# Ai_Breakout_BME280.net
KiCad netlist of a schematic drawn in EAGLE
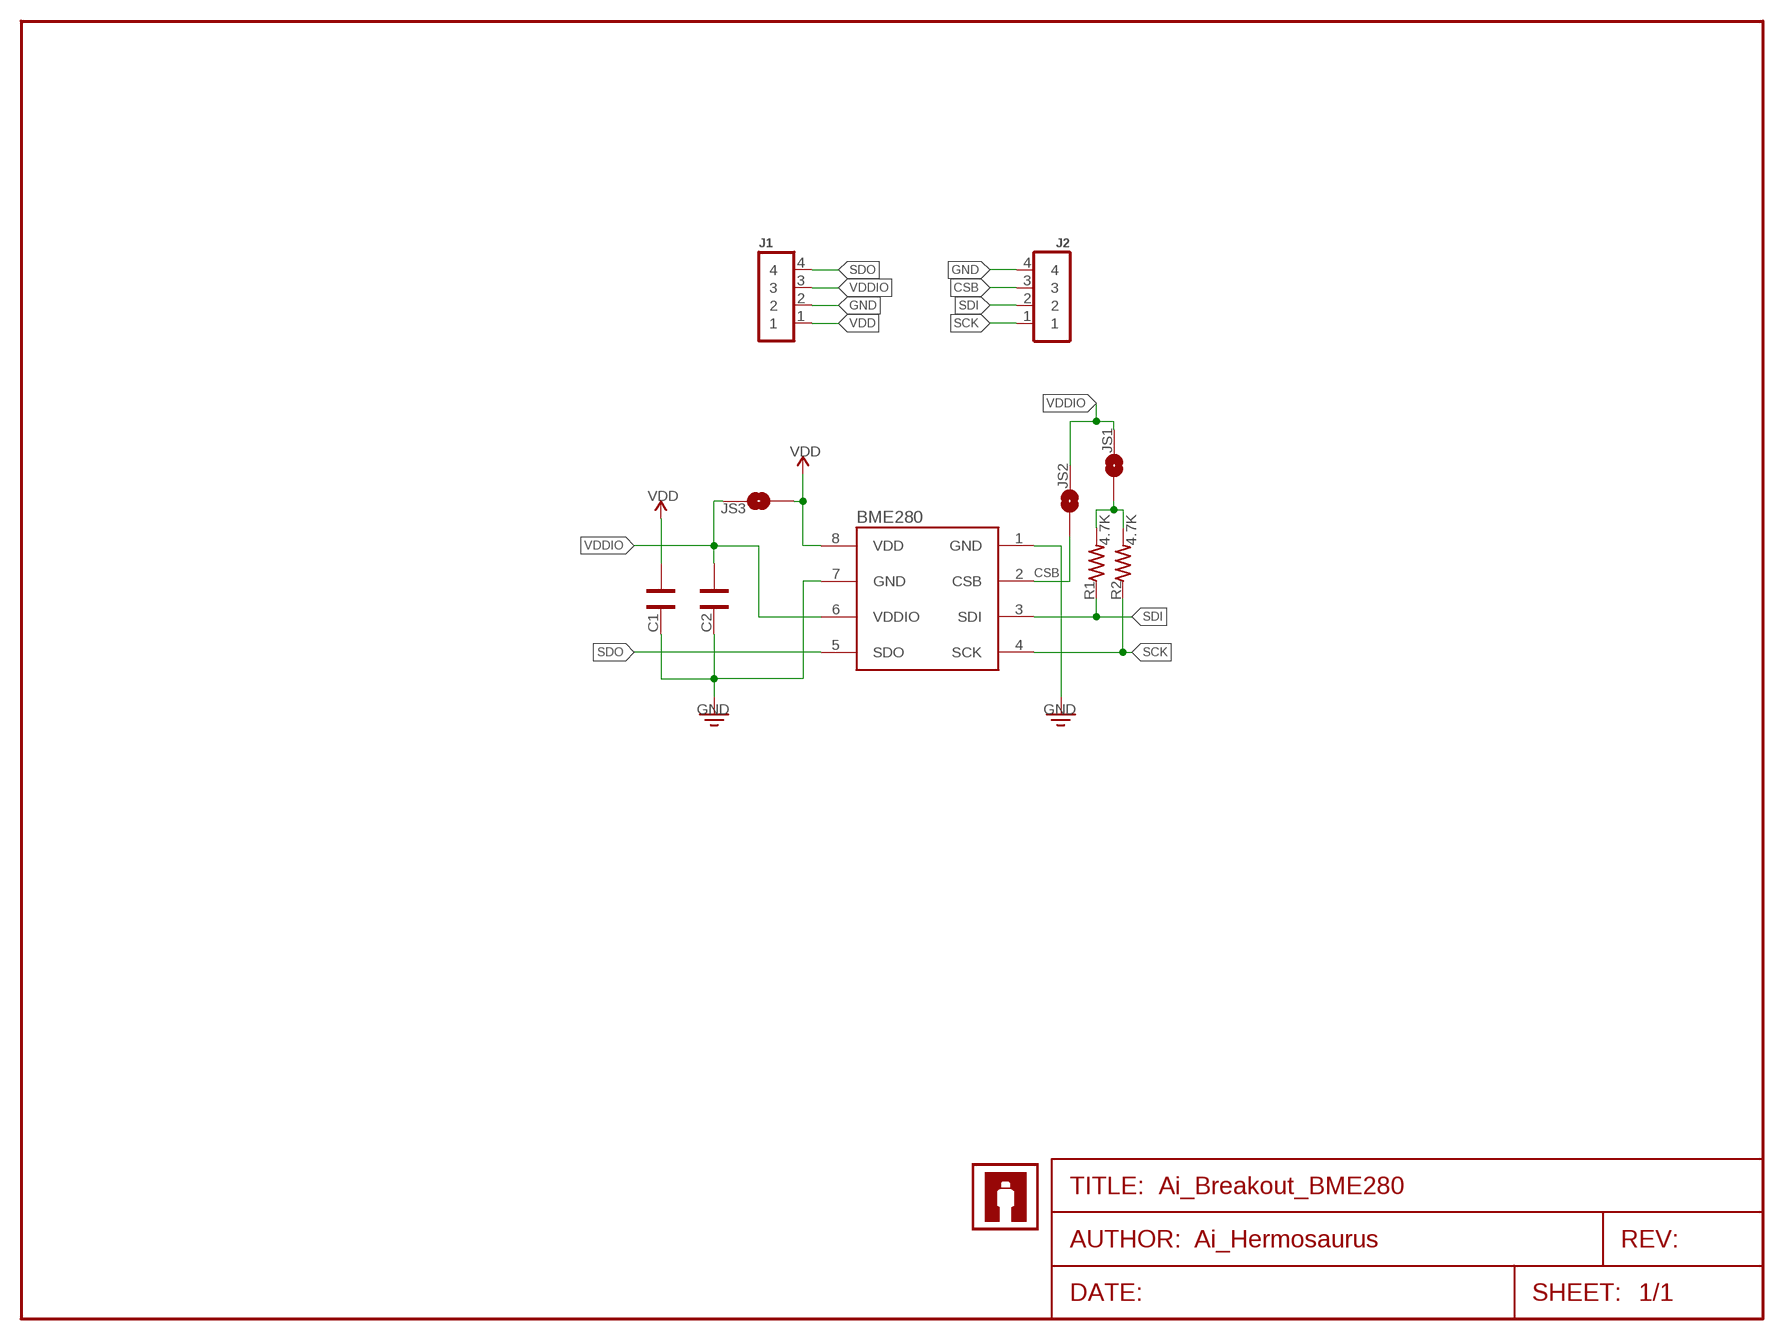
[diagram p0: schematic, sheet 1]

(export (version "E")
  (design (tool "Eeschema 10.0.6"))
  (components
    (comp (ref "C1")
      (value "CAP0603")
      (footprint "eagle-import:CAP-0603")
      (libsource (lib "eagle-import") (part "CAP0603"))
    )
    (comp (ref "C2")
      (value "CAP0603")
      (footprint "eagle-import:CAP-0603")
      (libsource (lib "eagle-import") (part "CAP0603"))
    )
    (comp (ref "J1")
      (value "1X04")
      (footprint "eagle-import:1X04")
      (libsource (lib "eagle-import") (part "1X04"))
    )
    (comp (ref "J2")
      (value "1X04NOFIRST")
      (footprint "eagle-import:1X04-NOFIRST")
      (libsource (lib "eagle-import") (part "1X04NOFIRST"))
    )
    (comp (ref "JS1")
      (value "1X02-SJ-NO")
      (footprint "eagle-import:1X02-SJ-NO")
      (libsource (lib "eagle-import") (part "1X02-SJ-NO"))
    )
    (comp (ref "JS2")
      (value "1X02-SJ-NO")
      (footprint "eagle-import:1X02-SJ-NO")
      (libsource (lib "eagle-import") (part "1X02-SJ-NO"))
    )
    (comp (ref "JS3")
      (value "1X02-SJ-NO")
      (footprint "eagle-import:1X02-SJ-NO")
      (libsource (lib "eagle-import") (part "1X02-SJ-NO"))
    )
    (comp (ref "R1")
      (value "4.7K")
      (footprint "eagle-import:RES-0603")
      (libsource (lib "eagle-import") (part "RES0603"))
    )
    (comp (ref "R2")
      (value "4.7K")
      (footprint "eagle-import:RES-0603")
      (libsource (lib "eagle-import") (part "RES0603"))
    )
    (comp (ref "U$2")
      (value "AI-LOGOXS")
      (footprint "eagle-import:AI-LOGO-XS")
      (libsource (lib "eagle-import") (part "AI-LOGOXS"))
    )
    (comp (ref "U1")
      (value "BME280")
      (footprint "eagle-import:BME280")
      (libsource (lib "eagle-import") (part "BME280"))
    )
  )
  (nets
    (net (code "1") (name "CSB") (class "Default")
      (node (ref "J2") (pin "3") (pinfunction "3_3") (pintype "bidirectional"))
      (node (ref "JS2") (pin "1") (pinfunction "1_1") (pintype "passive"))
      (node (ref "U1") (pin "2") (pinfunction "CSB_2") (pintype "power_in"))
    )
    (net (code "2") (name "GND") (class "Default")
      (node (ref "C1") (pin "2") (pinfunction "2_2") (pintype "passive"))
      (node (ref "C2") (pin "2") (pinfunction "2_2") (pintype "passive"))
      (node (ref "J1") (pin "2") (pinfunction "2_2") (pintype "bidirectional"))
      (node (ref "J2") (pin "4") (pinfunction "4_4") (pintype "bidirectional"))
      (node (ref "U1") (pin "1") (pinfunction "GND_1") (pintype "power_in"))
      (node (ref "U1") (pin "7") (pinfunction "GND_7") (pintype "power_in"))
    )
    (net (code "3") (name "Net-(JS1-Pad1)") (class "Default")
      (node (ref "JS1") (pin "1") (pinfunction "1_1") (pintype "passive"))
      (node (ref "R1") (pin "2") (pinfunction "2_2") (pintype "passive"))
      (node (ref "R2") (pin "2") (pinfunction "2_2") (pintype "passive"))
    )
    (net (code "4") (name "SCK") (class "Default")
      (node (ref "J2") (pin "1") (pinfunction "1_1") (pintype "bidirectional"))
      (node (ref "R2") (pin "1") (pinfunction "1_1") (pintype "passive"))
      (node (ref "U1") (pin "4") (pinfunction "SCK_4") (pintype "input"))
    )
    (net (code "5") (name "SDI") (class "Default")
      (node (ref "J2") (pin "2") (pinfunction "2_2") (pintype "bidirectional"))
      (node (ref "R1") (pin "1") (pinfunction "1_1") (pintype "passive"))
      (node (ref "U1") (pin "3") (pinfunction "SDI_3") (pintype "input"))
    )
    (net (code "6") (name "SDO") (class "Default")
      (node (ref "J1") (pin "4") (pinfunction "4_4") (pintype "bidirectional"))
      (node (ref "U1") (pin "5") (pinfunction "SDO_5") (pintype "bidirectional"))
    )
    (net (code "7") (name "VDD") (class "Default")
      (node (ref "C1") (pin "1") (pinfunction "1_1") (pintype "passive"))
      (node (ref "J1") (pin "1") (pinfunction "1_1") (pintype "bidirectional"))
      (node (ref "JS3") (pin "1") (pinfunction "1_1") (pintype "passive"))
      (node (ref "U1") (pin "8") (pinfunction "VDD_8") (pintype "power_in"))
    )
    (net (code "8") (name "VDDIO") (class "Default")
      (node (ref "C2") (pin "1") (pinfunction "1_1") (pintype "passive"))
      (node (ref "J1") (pin "3") (pinfunction "3_3") (pintype "bidirectional"))
      (node (ref "JS1") (pin "2") (pinfunction "2_2") (pintype "passive"))
      (node (ref "JS2") (pin "2") (pinfunction "2_2") (pintype "passive"))
      (node (ref "JS3") (pin "2") (pinfunction "2_2") (pintype "passive"))
      (node (ref "U1") (pin "6") (pinfunction "VDDIO_6") (pintype "power_in"))
    )
  )
)
